# MotorControllerVersion1.net
KiCad netlist of a schematic drawn in EAGLE
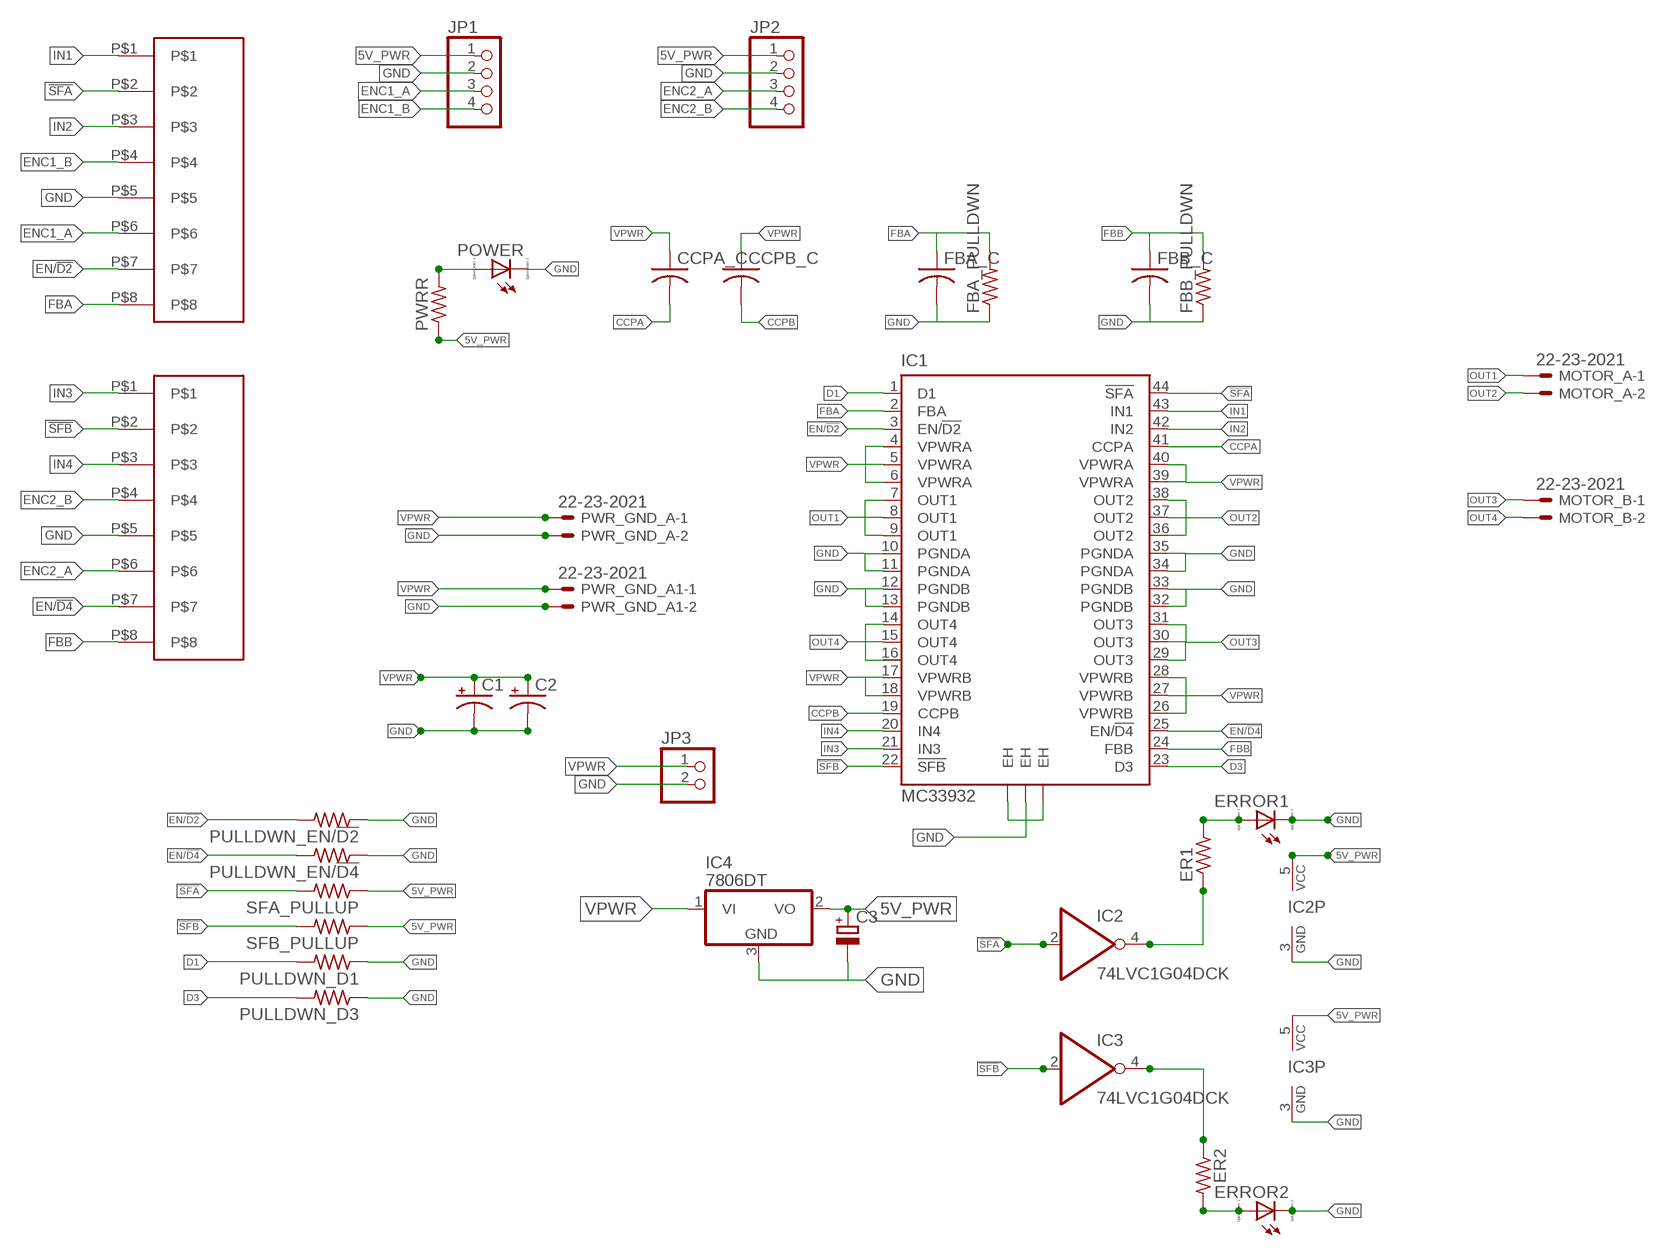
[diagram p0: schematic, sheet 1]

(export (version "E")
  (design (tool "Eeschema 10.0.6"))
  (components
    (comp (ref "C1")
      (value "CPOL-US153CLV-0810")
      (footprint "eagle-import:153CLV-0810")
      (libsource (lib "eagle-import") (part "CPOL-US153CLV-0810"))
    )
    (comp (ref "C2")
      (value "CPOL-US153CLV-0810")
      (footprint "eagle-import:153CLV-0810")
      (libsource (lib "eagle-import") (part "CPOL-US153CLV-0810"))
    )
    (comp (ref "C3")
      (value "CPOL-EU153CLV-0405")
      (footprint "eagle-import:153CLV-0405")
      (libsource (lib "eagle-import") (part "CPOL-EU153CLV-0405"))
    )
    (comp (ref "CCPA_C")
      (value "C-USC0805")
      (footprint "eagle-import:C0805")
      (libsource (lib "eagle-import") (part "C-USC0805"))
    )
    (comp (ref "CCPB_C")
      (value "C-USC0805")
      (footprint "eagle-import:C0805")
      (libsource (lib "eagle-import") (part "C-USC0805"))
    )
    (comp (ref "ER1")
      (value "R-US_R0805")
      (footprint "eagle-import:R0805")
      (libsource (lib "eagle-import") (part "R-US_R0805"))
    )
    (comp (ref "ER2")
      (value "R-US_R0805")
      (footprint "eagle-import:R0805")
      (libsource (lib "eagle-import") (part "R-US_R0805"))
    )
    (comp (ref "ERROR1")
      (value "LED_E")
      (footprint "eagle-import:LED_1206")
      (libsource (lib "eagle-import") (part "LED_E"))
    )
    (comp (ref "ERROR2")
      (value "LED_E")
      (footprint "eagle-import:LED_1206")
      (libsource (lib "eagle-import") (part "LED_E"))
    )
    (comp (ref "FBA_C")
      (value "C-USC0805")
      (footprint "eagle-import:C0805")
      (libsource (lib "eagle-import") (part "C-USC0805"))
    )
    (comp (ref "FBA_PULLDWN")
      (value "R-US_R0805")
      (footprint "eagle-import:R0805")
      (libsource (lib "eagle-import") (part "R-US_R0805"))
    )
    (comp (ref "FBB_C")
      (value "C-USC0805")
      (footprint "eagle-import:C0805")
      (libsource (lib "eagle-import") (part "C-USC0805"))
    )
    (comp (ref "FBB_PULLDWN")
      (value "R-US_R0805")
      (footprint "eagle-import:R0805")
      (libsource (lib "eagle-import") (part "R-US_R0805"))
    )
    (comp (ref "IC1")
      (value "MC33932")
      (footprint "eagle-import:HSOP44")
      (fields (field (name "MPN") "MC33932VW"))
      (libsource (lib "eagle-import") (part "MC33932"))
    )
    (comp (ref "IC2")
      (value "74LVC1G04DCK")
      (footprint "eagle-import:SC70-5")
      (libsource (lib "eagle-import") (part "741G04DCKLVC"))
    )
    (comp (ref "IC3")
      (value "74LVC1G04DCK")
      (footprint "eagle-import:SC70-5")
      (libsource (lib "eagle-import") (part "741G04DCKLVC"))
    )
    (comp (ref "IC4")
      (value "7806DT")
      (footprint "eagle-import:TO252")
      (libsource (lib "eagle-import") (part "78DT06"))
    )
    (comp (ref "JP1")
      (value "PINHD-1X4")
      (footprint "eagle-import:1X04")
      (libsource (lib "eagle-import") (part "PINHD-1X4"))
    )
    (comp (ref "JP2")
      (value "PINHD-1X4")
      (footprint "eagle-import:1X04")
      (libsource (lib "eagle-import") (part "PINHD-1X4"))
    )
    (comp (ref "JP3")
      (value "PINHD-1X2")
      (footprint "eagle-import:1X02")
      (libsource (lib "eagle-import") (part "PINHD-1X2"))
    )
    (comp (ref "MOTOR_A")
      (value "22-23-2021")
      (footprint "eagle-import:22-23-2021")
      (fields (field (name "MF") "MOLEX"))
      (libsource (lib "eagle-import") (part "22-23-2021"))
    )
    (comp (ref "MOTOR_B")
      (value "22-23-2021")
      (footprint "eagle-import:22-23-2021")
      (fields (field (name "MF") "MOLEX"))
      (libsource (lib "eagle-import") (part "22-23-2021"))
    )
    (comp (ref "POWER")
      (value "LED_E")
      (footprint "eagle-import:LED_1206")
      (libsource (lib "eagle-import") (part "LED_E"))
    )
    (comp (ref "PULLDWN_D1")
      (value "R-US_R0805")
      (footprint "eagle-import:R0805")
      (libsource (lib "eagle-import") (part "R-US_R0805"))
    )
    (comp (ref "PULLDWN_D3")
      (value "R-US_R0805")
      (footprint "eagle-import:R0805")
      (libsource (lib "eagle-import") (part "R-US_R0805"))
    )
    (comp (ref "PULLDWN_EN/!D2")
      (value "R-US_R0805")
      (footprint "eagle-import:R0805")
      (libsource (lib "eagle-import") (part "R-US_R0805"))
    )
    (comp (ref "PULLDWN_EN/!D4")
      (value "R-US_R0805")
      (footprint "eagle-import:R0805")
      (libsource (lib "eagle-import") (part "R-US_R0805"))
    )
    (comp (ref "PWRR")
      (value "R-US_R0805")
      (footprint "eagle-import:R0805")
      (libsource (lib "eagle-import") (part "R-US_R0805"))
    )
    (comp (ref "PWR_GND_A")
      (value "22-23-2021")
      (footprint "eagle-import:22-23-2021")
      (fields (field (name "MF") "MOLEX"))
      (libsource (lib "eagle-import") (part "22-23-2021"))
    )
    (comp (ref "PWR_GND_A1")
      (value "22-23-2021")
      (footprint "eagle-import:22-23-2021")
      (fields (field (name "MF") "MOLEX"))
      (libsource (lib "eagle-import") (part "22-23-2021"))
    )
    (comp (ref "SFA_PULLUP")
      (value "R-US_R0805")
      (footprint "eagle-import:R0805")
      (libsource (lib "eagle-import") (part "R-US_R0805"))
    )
    (comp (ref "SFB_PULLUP")
      (value "R-US_R0805")
      (footprint "eagle-import:R0805")
      (libsource (lib "eagle-import") (part "R-US_R0805"))
    )
    (comp (ref "U$1")
      (value "ETHERNETPORT")
      (footprint "eagle-import:ETHERNETPORT")
      (libsource (lib "eagle-import") (part "ETHERNETPORT"))
    )
    (comp (ref "U$2")
      (value "ETHERNETPORT")
      (footprint "eagle-import:ETHERNETPORT")
      (libsource (lib "eagle-import") (part "ETHERNETPORT"))
    )
  )
  (nets
    (net (code "1") (name "/EN{slash}~{D2}") (class "Default")
      (node (ref "IC1") (pin "3") (pinfunction "EN/~{D2}_3") (pintype "input"))
      (node (ref "PULLDWN_EN/!D2") (pin "2") (pinfunction "2_2") (pintype "passive"))
      (node (ref "U$1") (pin "P$7") (pinfunction "P$7_P$7") (pintype "bidirectional"))
    )
    (net (code "2") (name "/EN{slash}~{D4}") (class "Default")
      (node (ref "IC1") (pin "25") (pinfunction "EN/~{D4}_25") (pintype "input"))
      (node (ref "PULLDWN_EN/!D4") (pin "2") (pinfunction "2_2") (pintype "passive"))
      (node (ref "U$2") (pin "P$7") (pinfunction "P$7_P$7") (pintype "bidirectional"))
    )
    (net (code "3") (name "/~{SFA}") (class "Default")
      (node (ref "IC1") (pin "44") (pinfunction "~{SFA}_44") (pintype "open_collector"))
      (node (ref "IC2") (pin "2") (pinfunction "I_2") (pintype "input"))
      (node (ref "SFA_PULLUP") (pin "2") (pinfunction "2_2") (pintype "passive"))
      (node (ref "U$1") (pin "P$2") (pinfunction "P$2_P$2") (pintype "bidirectional"))
    )
    (net (code "4") (name "/~{SFB}") (class "Default")
      (node (ref "IC1") (pin "22") (pinfunction "~{SFB}_22") (pintype "open_collector"))
      (node (ref "IC3") (pin "2") (pinfunction "I_2") (pintype "input"))
      (node (ref "SFB_PULLUP") (pin "2") (pinfunction "2_2") (pintype "passive"))
      (node (ref "U$2") (pin "P$2") (pinfunction "P$2_P$2") (pintype "bidirectional"))
    )
    (net (code "5") (name "5V_PWR") (class "Default")
      (node (ref "C3") (pin "+") (pinfunction "+_+") (pintype "passive"))
      (node (ref "IC2") (pin "5") (pinfunction "VCC_5") (pintype "power_in"))
      (node (ref "IC3") (pin "5") (pinfunction "VCC_5") (pintype "power_in"))
      (node (ref "IC4") (pin "2") (pinfunction "VO_2") (pintype "passive"))
      (node (ref "JP1") (pin "1") (pinfunction "1_1") (pintype "passive"))
      (node (ref "JP2") (pin "1") (pinfunction "1_1") (pintype "passive"))
      (node (ref "PWRR") (pin "1") (pinfunction "1_1") (pintype "passive"))
      (node (ref "SFA_PULLUP") (pin "1") (pinfunction "1_1") (pintype "passive"))
      (node (ref "SFB_PULLUP") (pin "1") (pinfunction "1_1") (pintype "passive"))
    )
    (net (code "6") (name "CCPA") (class "Default")
      (node (ref "CCPA_C") (pin "2") (pinfunction "2_2") (pintype "passive"))
      (node (ref "IC1") (pin "41") (pinfunction "CCPA_41") (pintype "output"))
    )
    (net (code "7") (name "CCPB") (class "Default")
      (node (ref "CCPB_C") (pin "2") (pinfunction "2_2") (pintype "passive"))
      (node (ref "IC1") (pin "19") (pinfunction "CCPB_19") (pintype "output"))
    )
    (net (code "8") (name "D1") (class "Default")
      (node (ref "IC1") (pin "1") (pinfunction "D1_1") (pintype "input"))
      (node (ref "PULLDWN_D1") (pin "2") (pinfunction "2_2") (pintype "passive"))
    )
    (net (code "9") (name "D3") (class "Default")
      (node (ref "IC1") (pin "23") (pinfunction "D3_23") (pintype "input"))
      (node (ref "PULLDWN_D3") (pin "2") (pinfunction "2_2") (pintype "passive"))
    )
    (net (code "10") (name "ENC1_A") (class "Default")
      (node (ref "JP1") (pin "3") (pinfunction "3_3") (pintype "passive"))
      (node (ref "U$1") (pin "P$6") (pinfunction "P$6_P$6") (pintype "bidirectional"))
    )
    (net (code "11") (name "ENC1_B") (class "Default")
      (node (ref "JP1") (pin "4") (pinfunction "4_4") (pintype "passive"))
      (node (ref "U$1") (pin "P$4") (pinfunction "P$4_P$4") (pintype "bidirectional"))
    )
    (net (code "12") (name "ENC2_A") (class "Default")
      (node (ref "JP2") (pin "3") (pinfunction "3_3") (pintype "passive"))
      (node (ref "U$2") (pin "P$6") (pinfunction "P$6_P$6") (pintype "bidirectional"))
    )
    (net (code "13") (name "ENC2_B") (class "Default")
      (node (ref "JP2") (pin "4") (pinfunction "4_4") (pintype "passive"))
      (node (ref "U$2") (pin "P$4") (pinfunction "P$4_P$4") (pintype "bidirectional"))
    )
    (net (code "14") (name "FBA") (class "Default")
      (node (ref "FBA_C") (pin "1") (pinfunction "1_1") (pintype "passive"))
      (node (ref "FBA_PULLDWN") (pin "2") (pinfunction "2_2") (pintype "passive"))
      (node (ref "IC1") (pin "2") (pinfunction "FBA_2") (pintype "output"))
      (node (ref "U$1") (pin "P$8") (pinfunction "P$8_P$8") (pintype "bidirectional"))
    )
    (net (code "15") (name "FBB") (class "Default")
      (node (ref "FBB_C") (pin "1") (pinfunction "1_1") (pintype "passive"))
      (node (ref "FBB_PULLDWN") (pin "2") (pinfunction "2_2") (pintype "passive"))
      (node (ref "IC1") (pin "24") (pinfunction "FBB_24") (pintype "output"))
      (node (ref "U$2") (pin "P$8") (pinfunction "P$8_P$8") (pintype "bidirectional"))
    )
    (net (code "16") (name "GND") (class "Default")
      (node (ref "C1") (pin "-") (pinfunction "-_-") (pintype "passive"))
      (node (ref "C2") (pin "-") (pinfunction "-_-") (pintype "passive"))
      (node (ref "C3") (pin "-") (pinfunction "-_-") (pintype "passive"))
      (node (ref "ERROR1") (pin "C") (pinfunction "C_C") (pintype "passive"))
      (node (ref "ERROR2") (pin "C") (pinfunction "C_C") (pintype "passive"))
      (node (ref "FBA_C") (pin "2") (pinfunction "2_2") (pintype "passive"))
      (node (ref "FBA_PULLDWN") (pin "1") (pinfunction "1_1") (pintype "passive"))
      (node (ref "FBB_C") (pin "2") (pinfunction "2_2") (pintype "passive"))
      (node (ref "FBB_PULLDWN") (pin "1") (pinfunction "1_1") (pintype "passive"))
      (node (ref "IC1") (pin "10") (pinfunction "PGNDA_10") (pintype "power_in"))
      (node (ref "IC1") (pin "11") (pinfunction "PGNDA_11") (pintype "power_in"))
      (node (ref "IC1") (pin "12") (pinfunction "PGNDB_12") (pintype "power_in"))
      (node (ref "IC1") (pin "13") (pinfunction "PGNDB_13") (pintype "power_in"))
      (node (ref "IC1") (pin "32") (pinfunction "PGNDB_32") (pintype "power_in"))
      (node (ref "IC1") (pin "33") (pinfunction "PGNDB_33") (pintype "power_in"))
      (node (ref "IC1") (pin "34") (pinfunction "PGNDA_34") (pintype "power_in"))
      (node (ref "IC1") (pin "35") (pinfunction "PGNDA_35") (pintype "power_in"))
      (node (ref "IC1") (pin "EH@1") (pinfunction "EH_EH@1") (pintype "passive"))
      (node (ref "IC1") (pin "EH@2") (pinfunction "EH_EH@2") (pintype "passive"))
      (node (ref "IC1") (pin "EH@3") (pinfunction "EH_EH@3") (pintype "passive"))
      (node (ref "IC2") (pin "3") (pinfunction "GND_3") (pintype "power_in"))
      (node (ref "IC3") (pin "3") (pinfunction "GND_3") (pintype "power_in"))
      (node (ref "IC4") (pin "3") (pinfunction "GND_3") (pintype "passive"))
      (node (ref "JP1") (pin "2") (pinfunction "2_2") (pintype "passive"))
      (node (ref "JP2") (pin "2") (pinfunction "2_2") (pintype "passive"))
      (node (ref "JP3") (pin "2") (pinfunction "2_2") (pintype "passive"))
      (node (ref "POWER") (pin "C") (pinfunction "C_C") (pintype "passive"))
      (node (ref "PULLDWN_D1") (pin "1") (pinfunction "1_1") (pintype "passive"))
      (node (ref "PULLDWN_D3") (pin "1") (pinfunction "1_1") (pintype "passive"))
      (node (ref "PULLDWN_EN/!D2") (pin "1") (pinfunction "1_1") (pintype "passive"))
      (node (ref "PULLDWN_EN/!D4") (pin "1") (pinfunction "1_1") (pintype "passive"))
      (node (ref "PWR_GND_A") (pin "2") (pinfunction "S_2") (pintype "passive"))
      (node (ref "PWR_GND_A1") (pin "2") (pinfunction "S_2") (pintype "passive"))
      (node (ref "U$1") (pin "P$5") (pinfunction "P$5_P$5") (pintype "bidirectional"))
      (node (ref "U$2") (pin "P$5") (pinfunction "P$5_P$5") (pintype "bidirectional"))
    )
    (net (code "17") (name "IN1") (class "Default")
      (node (ref "IC1") (pin "43") (pinfunction "IN1_43") (pintype "input"))
      (node (ref "U$1") (pin "P$1") (pinfunction "P$1_P$1") (pintype "bidirectional"))
    )
    (net (code "18") (name "IN2") (class "Default")
      (node (ref "IC1") (pin "42") (pinfunction "IN2_42") (pintype "input"))
      (node (ref "U$1") (pin "P$3") (pinfunction "P$3_P$3") (pintype "bidirectional"))
    )
    (net (code "19") (name "IN3") (class "Default")
      (node (ref "IC1") (pin "21") (pinfunction "IN3_21") (pintype "input"))
      (node (ref "U$2") (pin "P$1") (pinfunction "P$1_P$1") (pintype "bidirectional"))
    )
    (net (code "20") (name "IN4") (class "Default")
      (node (ref "IC1") (pin "20") (pinfunction "IN4_20") (pintype "input"))
      (node (ref "U$2") (pin "P$3") (pinfunction "P$3_P$3") (pintype "bidirectional"))
    )
    (net (code "21") (name "Net-(ER1-Pad2)") (class "Default")
      (node (ref "ER1") (pin "2") (pinfunction "2_2") (pintype "passive"))
      (node (ref "ERROR1") (pin "A") (pinfunction "A_A") (pintype "passive"))
    )
    (net (code "22") (name "Net-(ER2-Pad2)") (class "Default")
      (node (ref "ER2") (pin "2") (pinfunction "2_2") (pintype "passive"))
      (node (ref "ERROR2") (pin "A") (pinfunction "A_A") (pintype "passive"))
    )
    (net (code "23") (name "Net-(IC2A-O)") (class "Default")
      (node (ref "ER1") (pin "1") (pinfunction "1_1") (pintype "passive"))
      (node (ref "IC2") (pin "4") (pinfunction "O_4") (pintype "output"))
    )
    (net (code "24") (name "Net-(IC3A-O)") (class "Default")
      (node (ref "ER2") (pin "1") (pinfunction "1_1") (pintype "passive"))
      (node (ref "IC3") (pin "4") (pinfunction "O_4") (pintype "output"))
    )
    (net (code "25") (name "Net-(POWER-PadA)") (class "Default")
      (node (ref "POWER") (pin "A") (pinfunction "A_A") (pintype "passive"))
      (node (ref "PWRR") (pin "2") (pinfunction "2_2") (pintype "passive"))
    )
    (net (code "26") (name "OUT1") (class "Default")
      (node (ref "IC1") (pin "7") (pinfunction "OUT1_7") (pintype "output"))
      (node (ref "IC1") (pin "8") (pinfunction "OUT1_8") (pintype "passive"))
      (node (ref "IC1") (pin "9") (pinfunction "OUT1_9") (pintype "passive"))
      (node (ref "MOTOR_A") (pin "1") (pinfunction "S_1") (pintype "passive"))
    )
    (net (code "27") (name "OUT2") (class "Default")
      (node (ref "IC1") (pin "36") (pinfunction "OUT2_36") (pintype "output"))
      (node (ref "IC1") (pin "37") (pinfunction "OUT2_37") (pintype "passive"))
      (node (ref "IC1") (pin "38") (pinfunction "OUT2_38") (pintype "passive"))
      (node (ref "MOTOR_A") (pin "2") (pinfunction "S_2") (pintype "passive"))
    )
    (net (code "28") (name "OUT3") (class "Default")
      (node (ref "IC1") (pin "29") (pinfunction "OUT3_29") (pintype "output"))
      (node (ref "IC1") (pin "30") (pinfunction "OUT3_30") (pintype "passive"))
      (node (ref "IC1") (pin "31") (pinfunction "OUT3_31") (pintype "passive"))
      (node (ref "MOTOR_B") (pin "1") (pinfunction "S_1") (pintype "passive"))
    )
    (net (code "29") (name "OUT4") (class "Default")
      (node (ref "IC1") (pin "14") (pinfunction "OUT4_14") (pintype "output"))
      (node (ref "IC1") (pin "15") (pinfunction "OUT4_15") (pintype "passive"))
      (node (ref "IC1") (pin "16") (pinfunction "OUT4_16") (pintype "passive"))
      (node (ref "MOTOR_B") (pin "2") (pinfunction "S_2") (pintype "passive"))
    )
    (net (code "30") (name "VPWR") (class "Default")
      (node (ref "C1") (pin "+") (pinfunction "+_+") (pintype "passive"))
      (node (ref "C2") (pin "+") (pinfunction "+_+") (pintype "passive"))
      (node (ref "CCPA_C") (pin "1") (pinfunction "1_1") (pintype "passive"))
      (node (ref "CCPB_C") (pin "1") (pinfunction "1_1") (pintype "passive"))
      (node (ref "IC1") (pin "17") (pinfunction "VPWRB_17") (pintype "input"))
      (node (ref "IC1") (pin "18") (pinfunction "VPWRB_18") (pintype "input"))
      (node (ref "IC1") (pin "26") (pinfunction "VPWRB_26") (pintype "input"))
      (node (ref "IC1") (pin "27") (pinfunction "VPWRB_27") (pintype "input"))
      (node (ref "IC1") (pin "28") (pinfunction "VPWRB_28") (pintype "input"))
      (node (ref "IC1") (pin "39") (pinfunction "VPWRA_39") (pintype "input"))
      (node (ref "IC1") (pin "4") (pinfunction "VPWRA_4") (pintype "input"))
      (node (ref "IC1") (pin "40") (pinfunction "VPWRA_40") (pintype "input"))
      (node (ref "IC1") (pin "5") (pinfunction "VPWRA_5") (pintype "input"))
      (node (ref "IC1") (pin "6") (pinfunction "VPWRA_6") (pintype "input"))
      (node (ref "IC4") (pin "1") (pinfunction "VI_1") (pintype "input"))
      (node (ref "JP3") (pin "1") (pinfunction "1_1") (pintype "passive"))
      (node (ref "PWR_GND_A") (pin "1") (pinfunction "S_1") (pintype "passive"))
      (node (ref "PWR_GND_A1") (pin "1") (pinfunction "S_1") (pintype "passive"))
    )
  )
)
